# audio_webcam_final.net
KiCad netlist of a schematic drawn in EAGLE
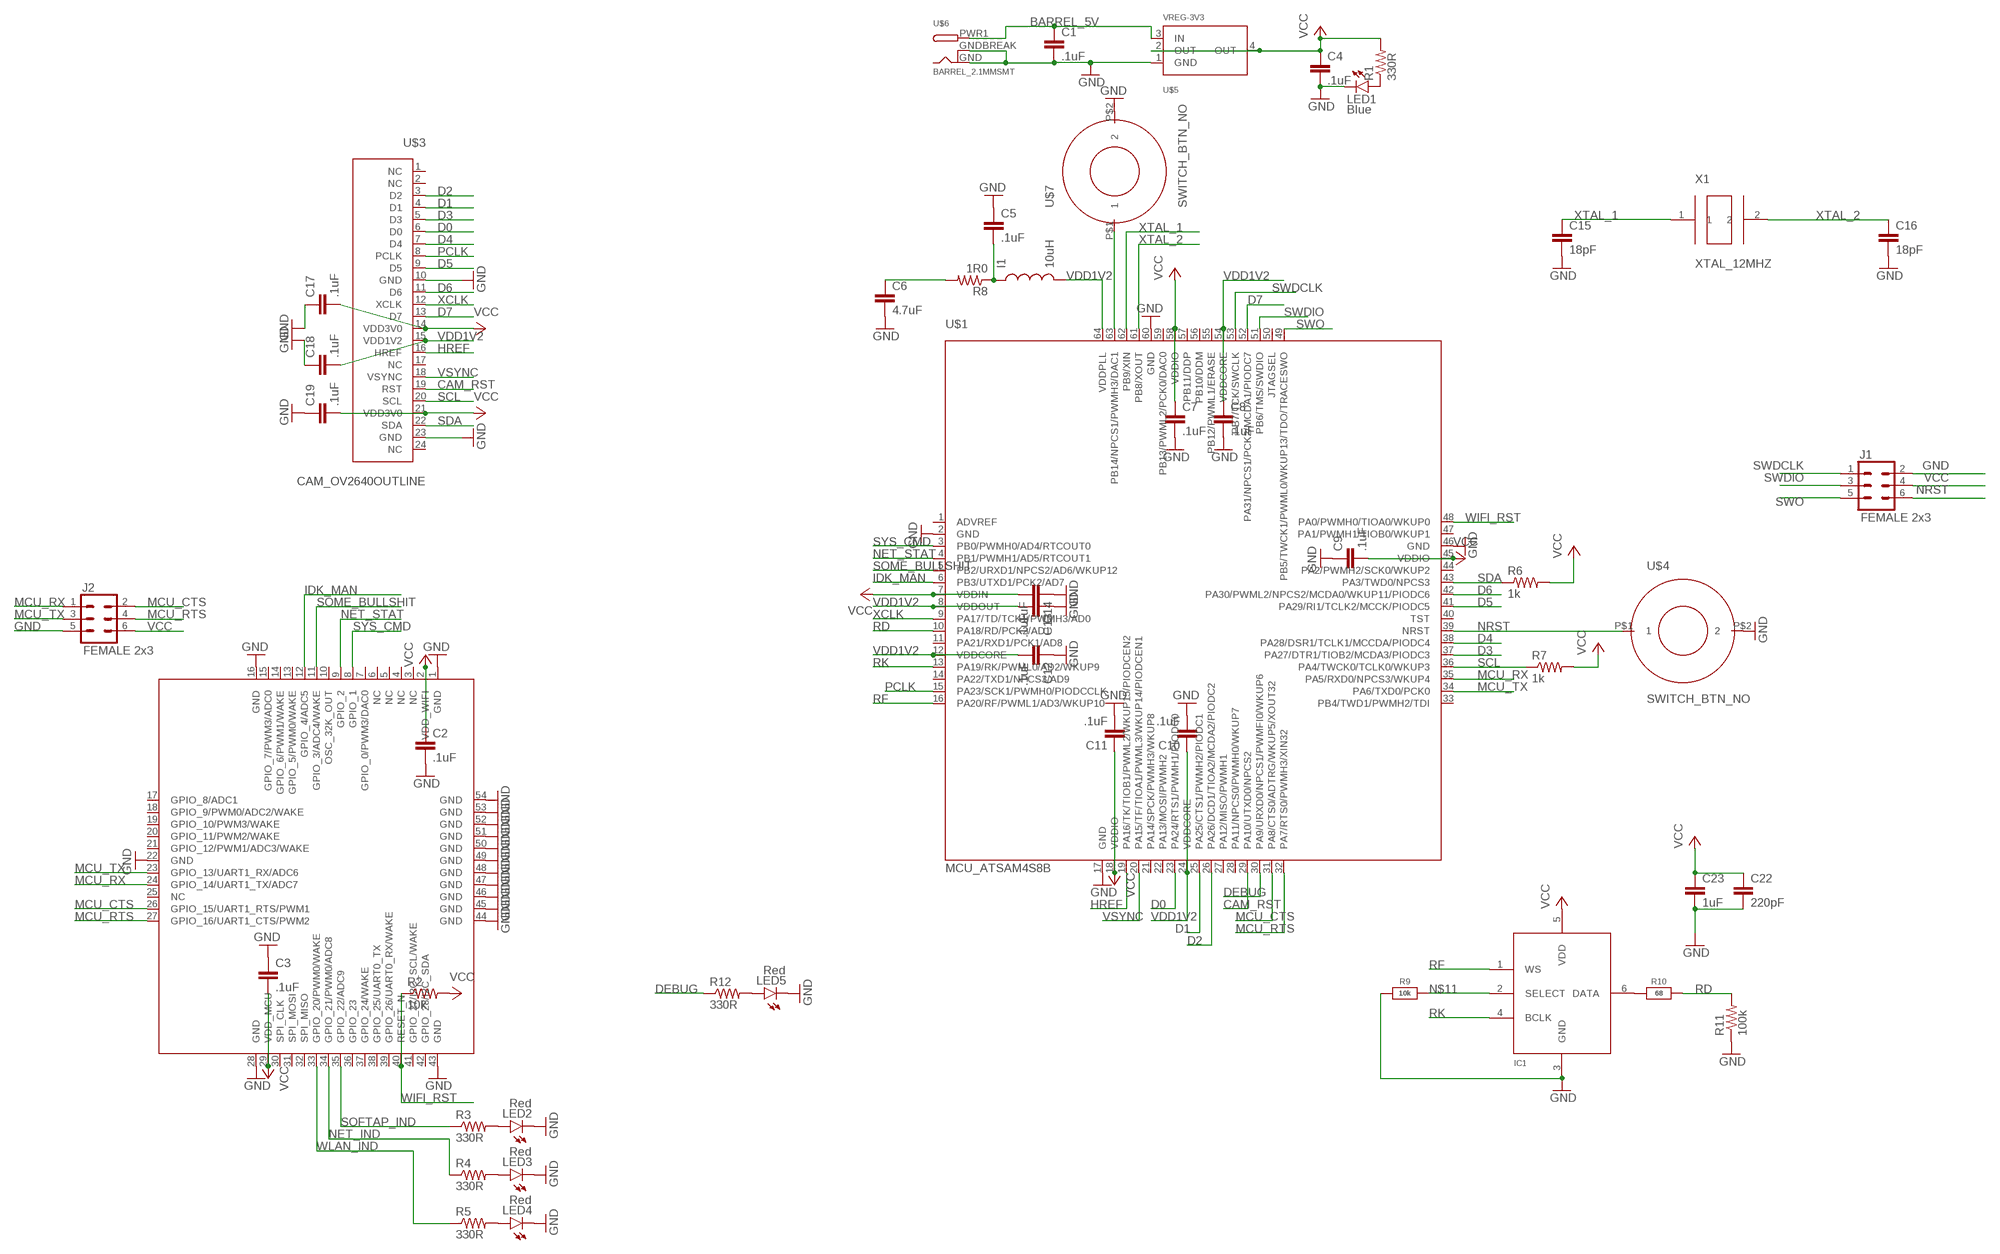
[diagram p0: schematic, sheet 1]

(export (version "E")
  (design (tool "Eeschema 10.0.6"))
  (components
    (comp (ref "C1")
      (value ".1uF")
      (footprint "eagle-import:0805")
      (libsource (lib "eagle-import") (part "CAP"))
    )
    (comp (ref "C2")
      (value ".1uF")
      (footprint "eagle-import:0805")
      (libsource (lib "eagle-import") (part "CAP"))
    )
    (comp (ref "C3")
      (value ".1uF")
      (footprint "eagle-import:0805")
      (libsource (lib "eagle-import") (part "CAP"))
    )
    (comp (ref "C4")
      (value ".1uF")
      (footprint "eagle-import:0805")
      (libsource (lib "eagle-import") (part "CAP"))
    )
    (comp (ref "C5")
      (value ".1uF")
      (footprint "eagle-import:0805")
      (libsource (lib "eagle-import") (part "CAP"))
    )
    (comp (ref "C6")
      (value "4.7uF")
      (footprint "eagle-import:0805")
      (libsource (lib "eagle-import") (part "CAP"))
    )
    (comp (ref "C7")
      (value ".1uF")
      (footprint "eagle-import:0805")
      (libsource (lib "eagle-import") (part "CAP"))
    )
    (comp (ref "C8")
      (value ".1uF")
      (footprint "eagle-import:0805")
      (libsource (lib "eagle-import") (part "CAP"))
    )
    (comp (ref "C9")
      (value ".1uF")
      (footprint "eagle-import:0805")
      (libsource (lib "eagle-import") (part "CAP"))
    )
    (comp (ref "C10")
      (value ".1uF")
      (footprint "eagle-import:0805")
      (libsource (lib "eagle-import") (part "CAP"))
    )
    (comp (ref "C11")
      (value ".1uF")
      (footprint "eagle-import:0805")
      (libsource (lib "eagle-import") (part "CAP"))
    )
    (comp (ref "C12")
      (value ".1uF")
      (footprint "eagle-import:0805")
      (libsource (lib "eagle-import") (part "CAP"))
    )
    (comp (ref "C13")
      (value ".1uF")
      (footprint "eagle-import:0805")
      (libsource (lib "eagle-import") (part "CAP"))
    )
    (comp (ref "C14")
      (value ".1uF")
      (footprint "eagle-import:0805")
      (libsource (lib "eagle-import") (part "CAP"))
    )
    (comp (ref "C15")
      (value "18pF")
      (footprint "eagle-import:0805")
      (libsource (lib "eagle-import") (part "CAP"))
    )
    (comp (ref "C16")
      (value "18pF")
      (footprint "eagle-import:0805")
      (libsource (lib "eagle-import") (part "CAP"))
    )
    (comp (ref "C17")
      (value ".1uF")
      (footprint "eagle-import:0805")
      (libsource (lib "eagle-import") (part "CAP"))
    )
    (comp (ref "C18")
      (value ".1uF")
      (footprint "eagle-import:0805")
      (libsource (lib "eagle-import") (part "CAP"))
    )
    (comp (ref "C19")
      (value ".1uF")
      (footprint "eagle-import:0805")
      (libsource (lib "eagle-import") (part "CAP"))
    )
    (comp (ref "C22")
      (value "220pF")
      (footprint "eagle-import:0805")
      (libsource (lib "eagle-import") (part "CAP"))
    )
    (comp (ref "C23")
      (value "1uF")
      (footprint "eagle-import:0805")
      (libsource (lib "eagle-import") (part "CAP"))
    )
    (comp (ref "I1")
      (value "10uH")
      (footprint "eagle-import:0805")
      (libsource (lib "eagle-import") (part "IND"))
    )
    (comp (ref "IC1")
      (value "MIC_I2S_SPH0645")
      (footprint "eagle-import:SPH0645LM4H")
      (libsource (lib "eagle-import") (part "MIC_I2S_SPH0645"))
    )
    (comp (ref "J1")
      (value "FEMALE 2x3")
      (footprint "eagle-import:2X3")
      (libsource (lib "eagle-import") (part "CONN_03X2FEMALE"))
    )
    (comp (ref "J2")
      (value "FEMALE 2x3")
      (footprint "eagle-import:2X3")
      (libsource (lib "eagle-import") (part "CONN_03X2FEMALE"))
    )
    (comp (ref "LED1")
      (value "Blue")
      (footprint "eagle-import:LED-0603")
      (libsource (lib "eagle-import") (part "LED0603"))
    )
    (comp (ref "LED2")
      (value "Red")
      (footprint "eagle-import:LED-0603")
      (libsource (lib "eagle-import") (part "LED0603"))
    )
    (comp (ref "LED3")
      (value "Red")
      (footprint "eagle-import:LED-0603")
      (libsource (lib "eagle-import") (part "LED0603"))
    )
    (comp (ref "LED4")
      (value "Red")
      (footprint "eagle-import:LED-0603")
      (libsource (lib "eagle-import") (part "LED0603"))
    )
    (comp (ref "LED5")
      (value "Red")
      (footprint "eagle-import:LED-0603")
      (libsource (lib "eagle-import") (part "LED0603"))
    )
    (comp (ref "R1")
      (value "330R")
      (footprint "eagle-import:0805")
      (libsource (lib "eagle-import") (part "RES"))
    )
    (comp (ref "R2")
      (value "10k")
      (footprint "eagle-import:0805")
      (libsource (lib "eagle-import") (part "RES"))
    )
    (comp (ref "R3")
      (value "330R")
      (footprint "eagle-import:0805")
      (libsource (lib "eagle-import") (part "RES"))
    )
    (comp (ref "R4")
      (value "330R")
      (footprint "eagle-import:0805")
      (libsource (lib "eagle-import") (part "RES"))
    )
    (comp (ref "R5")
      (value "330R")
      (footprint "eagle-import:0805")
      (libsource (lib "eagle-import") (part "RES"))
    )
    (comp (ref "R6")
      (value "1k")
      (footprint "eagle-import:0805")
      (libsource (lib "eagle-import") (part "RES"))
    )
    (comp (ref "R7")
      (value "1k")
      (footprint "eagle-import:0805")
      (libsource (lib "eagle-import") (part "RES"))
    )
    (comp (ref "R8")
      (value "1R0")
      (footprint "eagle-import:0805")
      (libsource (lib "eagle-import") (part "RES"))
    )
    (comp (ref "R9")
      (value "10k")
      (footprint "eagle-import:0603-NO")
      (libsource (lib "eagle-import") (part "RESISTOR_0603_NOOUT"))
    )
    (comp (ref "R10")
      (value "68")
      (footprint "eagle-import:0603-NO")
      (libsource (lib "eagle-import") (part "RESISTOR_0603_NOOUT"))
    )
    (comp (ref "R11")
      (value "100k")
      (footprint "eagle-import:0805")
      (libsource (lib "eagle-import") (part "RES"))
    )
    (comp (ref "R12")
      (value "330R")
      (footprint "eagle-import:0805")
      (libsource (lib "eagle-import") (part "RES"))
    )
    (comp (ref "U$1")
      (value "MCU_ATSAM4S8B")
      (footprint "eagle-import:QFP50P1200X1200X160-64N")
      (libsource (lib "eagle-import") (part "MCU_ATSAM4S8B"))
    )
    (comp (ref "U$2")
      (value "WIFI_AMW004")
      (footprint "eagle-import:AMW004")
      (libsource (lib "eagle-import") (part "WIFI_AMW004"))
    )
    (comp (ref "U$3")
      (value "CAM_OV2640OUTLINE")
      (footprint "eagle-import:CAM_CONN")
      (libsource (lib "eagle-import") (part "CAM_OV2640OUTLINE"))
    )
    (comp (ref "U$4")
      (value "SWITCH_BTN_NO")
      (footprint "eagle-import:BTN_2")
      (libsource (lib "eagle-import") (part "SWITCH_BTN_NO"))
    )
    (comp (ref "U$5")
      (value "VREG-3V3")
      (footprint "eagle-import:R-PDSO-G4_TI")
      (libsource (lib "eagle-import") (part "VREG-3V3"))
    )
    (comp (ref "U$6")
      (value "BARREL_2.1MMSMT")
      (footprint "eagle-import:DCJACK_2MM_SMT")
      (libsource (lib "eagle-import") (part "BARREL_2.1MMSMT"))
    )
    (comp (ref "U$7")
      (value "SWITCH_BTN_NO")
      (footprint "eagle-import:BTN_2")
      (libsource (lib "eagle-import") (part "SWITCH_BTN_NO"))
    )
    (comp (ref "X1")
      (value "XTAL_12MHZ")
      (footprint "eagle-import:ABM7-16.000MHZ-D2Y-T")
      (libsource (lib "eagle-import") (part "XTAL_12MHZ"))
    )
  )
  (nets
    (net (code "1") (name "/BARREL_5V") (class "Default")
      (node (ref "C1") (pin "1") (pinfunction "1_1") (pintype "passive"))
      (node (ref "U$5") (pin "3") (pinfunction "IN_3") (pintype "bidirectional"))
      (node (ref "U$6") (pin "PWR1") (pinfunction "PWR_PWR1") (pintype "power_in"))
    )
    (net (code "2") (name "/CAM_RST") (class "Default")
      (node (ref "U$1") (pin "29") (pinfunction "PA10/UTXD0/NPCS2_29") (pintype "bidirectional"))
      (node (ref "U$3") (pin "19") (pinfunction "RST_19") (pintype "bidirectional"))
    )
    (net (code "3") (name "/D0") (class "Default")
      (node (ref "U$1") (pin "23") (pinfunction "PA24/RTS1/PWMH1/PIODC0_23") (pintype "bidirectional"))
      (node (ref "U$3") (pin "6") (pinfunction "D0_6") (pintype "bidirectional"))
    )
    (net (code "4") (name "/D1") (class "Default")
      (node (ref "U$1") (pin "25") (pinfunction "PA25/CTS1/PWMH2/PIODC1_25") (pintype "bidirectional"))
      (node (ref "U$3") (pin "4") (pinfunction "D1_4") (pintype "bidirectional"))
    )
    (net (code "5") (name "/D2") (class "Default")
      (node (ref "U$1") (pin "26") (pinfunction "PA26/DCD1/TIOA2/MCDA2/PIODC2_26") (pintype "bidirectional"))
      (node (ref "U$3") (pin "3") (pinfunction "D2_3") (pintype "bidirectional"))
    )
    (net (code "6") (name "/D3") (class "Default")
      (node (ref "U$1") (pin "37") (pinfunction "PA27/DTR1/TIOB2/MCDA3/PIODC3_37") (pintype "bidirectional"))
      (node (ref "U$3") (pin "5") (pinfunction "D3_5") (pintype "bidirectional"))
    )
    (net (code "7") (name "/D4") (class "Default")
      (node (ref "U$1") (pin "38") (pinfunction "PA28/DSR1/TCLK1/MCCDA/PIODC4_38") (pintype "bidirectional"))
      (node (ref "U$3") (pin "7") (pinfunction "D4_7") (pintype "bidirectional"))
    )
    (net (code "8") (name "/D5") (class "Default")
      (node (ref "U$1") (pin "41") (pinfunction "PA29/RI1/TCLK2/MCCK/PIODC5_41") (pintype "bidirectional"))
      (node (ref "U$3") (pin "9") (pinfunction "D5_9") (pintype "bidirectional"))
    )
    (net (code "9") (name "/D6") (class "Default")
      (node (ref "U$1") (pin "42") (pinfunction "PA30/PWML2/NPCS2/MCDA0/WKUP11/PIODC6_42") (pintype "bidirectional"))
      (node (ref "U$3") (pin "11") (pinfunction "D6_11") (pintype "bidirectional"))
    )
    (net (code "10") (name "/D7") (class "Default")
      (node (ref "U$1") (pin "52") (pinfunction "PA31/NPCS1/PCK2/MCDA1/PIODC7_52") (pintype "bidirectional"))
      (node (ref "U$3") (pin "13") (pinfunction "D7_13") (pintype "bidirectional"))
    )
    (net (code "11") (name "/DEBUG") (class "Default")
      (node (ref "R12") (pin "1") (pinfunction "1_1") (pintype "passive"))
      (node (ref "U$1") (pin "30") (pinfunction "PA9/URXD0/NPCS1/PWMFI0/WKUP6_30") (pintype "bidirectional"))
    )
    (net (code "12") (name "/HREF") (class "Default")
      (node (ref "U$1") (pin "19") (pinfunction "PA16/TK/TIOB1/PWML2/WKUP15/PIODCEN2_19") (pintype "bidirectional"))
      (node (ref "U$3") (pin "16") (pinfunction "HREF_16") (pintype "bidirectional"))
    )
    (net (code "13") (name "/IDK_MAN") (class "Default")
      (node (ref "U$1") (pin "6") (pinfunction "PB3/UTXD1/PCK2/AD7_6") (pintype "bidirectional"))
      (node (ref "U$2") (pin "12") (pinfunction "GPIO_4/ADC5_12") (pintype "bidirectional"))
    )
    (net (code "14") (name "/MCU_CTS") (class "Default")
      (node (ref "J2") (pin "2") (pinfunction "2_2") (pintype "bidirectional"))
      (node (ref "U$1") (pin "31") (pinfunction "PA8/CTS0/ADTRG/WKUP5/XOUT32_31") (pintype "bidirectional"))
      (node (ref "U$2") (pin "26") (pinfunction "GPIO_15/UART1_RTS/PWM1_26") (pintype "bidirectional"))
    )
    (net (code "15") (name "/MCU_RTS") (class "Default")
      (node (ref "J2") (pin "4") (pinfunction "4_4") (pintype "bidirectional"))
      (node (ref "U$1") (pin "32") (pinfunction "PA7/RTS0/PWMH3/XIN32_32") (pintype "bidirectional"))
      (node (ref "U$2") (pin "27") (pinfunction "GPIO_16/UART1_CTS/PWM2_27") (pintype "bidirectional"))
    )
    (net (code "16") (name "/MCU_RX") (class "Default")
      (node (ref "J2") (pin "1") (pinfunction "1_1") (pintype "bidirectional"))
      (node (ref "U$1") (pin "35") (pinfunction "PA5/RXD0/NPCS3/WKUP4_35") (pintype "bidirectional"))
      (node (ref "U$2") (pin "24") (pinfunction "GPIO_14/UART1_TX/ADC7_24") (pintype "bidirectional"))
    )
    (net (code "17") (name "/MCU_TX") (class "Default")
      (node (ref "J2") (pin "3") (pinfunction "3_3") (pintype "bidirectional"))
      (node (ref "U$1") (pin "34") (pinfunction "PA6/TXD0/PCK0_34") (pintype "bidirectional"))
      (node (ref "U$2") (pin "23") (pinfunction "GPIO_13/UART1_RX/ADC6_23") (pintype "bidirectional"))
    )
    (net (code "18") (name "/N$11") (class "Default")
      (node (ref "IC1") (pin "2") (pinfunction "SELECT_2") (pintype "input"))
      (node (ref "R9") (pin "2") (pinfunction "2_2") (pintype "passive"))
    )
    (net (code "19") (name "/NET_IND") (class "Default")
      (node (ref "R4") (pin "1") (pinfunction "1_1") (pintype "passive"))
      (node (ref "U$2") (pin "34") (pinfunction "GPIO_21/PWM0/ADC8_34") (pintype "bidirectional"))
    )
    (net (code "20") (name "/NET_STAT") (class "Default")
      (node (ref "U$1") (pin "4") (pinfunction "PB1/PWMH1/AD5/RTCOUT1_4") (pintype "bidirectional"))
      (node (ref "U$2") (pin "9") (pinfunction "GPIO_2_9") (pintype "bidirectional"))
    )
    (net (code "21") (name "/NRST") (class "Default")
      (node (ref "J1") (pin "6") (pinfunction "6_6") (pintype "bidirectional"))
      (node (ref "U$1") (pin "39") (pinfunction "NRST_39") (pintype "bidirectional"))
      (node (ref "U$4") (pin "P$1") (pinfunction "1_P$1") (pintype "bidirectional"))
    )
    (net (code "22") (name "/PCLK") (class "Default")
      (node (ref "U$1") (pin "15") (pinfunction "PA23/SCK1/PWMH0/PIODCCLK_15") (pintype "bidirectional"))
      (node (ref "U$3") (pin "8") (pinfunction "PCLK_8") (pintype "bidirectional"))
    )
    (net (code "23") (name "/RD") (class "Default")
      (node (ref "R10") (pin "2") (pinfunction "2_2") (pintype "passive"))
      (node (ref "R11") (pin "2") (pinfunction "2_2") (pintype "passive"))
      (node (ref "U$1") (pin "10") (pinfunction "PA18/RD/PCK2/AD1_10") (pintype "bidirectional"))
    )
    (net (code "24") (name "/RF") (class "Default")
      (node (ref "IC1") (pin "1") (pinfunction "WS_1") (pintype "input"))
      (node (ref "U$1") (pin "16") (pinfunction "PA20/RF/PWML1/AD3/WKUP10_16") (pintype "bidirectional"))
    )
    (net (code "25") (name "/RK") (class "Default")
      (node (ref "IC1") (pin "4") (pinfunction "BCLK_4") (pintype "input"))
      (node (ref "U$1") (pin "13") (pinfunction "PA19/RK/PWML0/AD2/WKUP9_13") (pintype "bidirectional"))
    )
    (net (code "26") (name "/SCL") (class "Default")
      (node (ref "R7") (pin "1") (pinfunction "1_1") (pintype "passive"))
      (node (ref "U$1") (pin "36") (pinfunction "PA4/TWCK0/TCLK0/WKUP3_36") (pintype "bidirectional"))
      (node (ref "U$3") (pin "20") (pinfunction "SCL_20") (pintype "bidirectional"))
    )
    (net (code "27") (name "/SDA") (class "Default")
      (node (ref "R6") (pin "1") (pinfunction "1_1") (pintype "passive"))
      (node (ref "U$1") (pin "43") (pinfunction "PA3/TWD0/NPCS3_43") (pintype "bidirectional"))
      (node (ref "U$3") (pin "22") (pinfunction "SDA_22") (pintype "bidirectional"))
    )
    (net (code "28") (name "/SOFTAP_IND") (class "Default")
      (node (ref "R3") (pin "1") (pinfunction "1_1") (pintype "passive"))
      (node (ref "U$2") (pin "35") (pinfunction "GPIO_22/ADC9_35") (pintype "bidirectional"))
    )
    (net (code "29") (name "/SOME_BULLSHIT") (class "Default")
      (node (ref "U$1") (pin "5") (pinfunction "PB2/URXD1/NPCS2/AD6/WKUP12_5") (pintype "bidirectional"))
      (node (ref "U$2") (pin "11") (pinfunction "GPIO_3/ADC4/WAKE_11") (pintype "bidirectional"))
    )
    (net (code "30") (name "/SWDCLK") (class "Default")
      (node (ref "J1") (pin "1") (pinfunction "1_1") (pintype "bidirectional"))
      (node (ref "U$1") (pin "53") (pinfunction "PB7/TCK/SWCLK_53") (pintype "bidirectional"))
    )
    (net (code "31") (name "/SWDIO") (class "Default")
      (node (ref "J1") (pin "3") (pinfunction "3_3") (pintype "bidirectional"))
      (node (ref "U$1") (pin "51") (pinfunction "PB6/TMS/SWDIO_51") (pintype "bidirectional"))
    )
    (net (code "32") (name "/SWO") (class "Default")
      (node (ref "J1") (pin "5") (pinfunction "5_5") (pintype "bidirectional"))
      (node (ref "U$1") (pin "49") (pinfunction "PB5/TWCK1/PWML0/WKUP13/TDO/TRACESWO_49") (pintype "bidirectional"))
    )
    (net (code "33") (name "/SYS_CMD") (class "Default")
      (node (ref "U$1") (pin "3") (pinfunction "PB0/PWMH0/AD4/RTCOUT0_3") (pintype "bidirectional"))
      (node (ref "U$2") (pin "8") (pinfunction "GPIO_1_8") (pintype "bidirectional"))
    )
    (net (code "34") (name "/VDD1V2") (class "Default")
      (node (ref "C10") (pin "1") (pinfunction "1_1") (pintype "passive"))
      (node (ref "C12") (pin "2") (pinfunction "2_2") (pintype "passive"))
      (node (ref "C13") (pin "2") (pinfunction "2_2") (pintype "passive"))
      (node (ref "C18") (pin "2") (pinfunction "2_2") (pintype "passive"))
      (node (ref "C8") (pin "1") (pinfunction "1_1") (pintype "passive"))
      (node (ref "I1") (pin "2") (pinfunction "2_2") (pintype "passive"))
      (node (ref "U$1") (pin "12") (pinfunction "VDDCORE_12") (pintype "bidirectional"))
      (node (ref "U$1") (pin "24") (pinfunction "VDDCORE_24") (pintype "bidirectional"))
      (node (ref "U$1") (pin "54") (pinfunction "VDDCORE_54") (pintype "bidirectional"))
      (node (ref "U$1") (pin "64") (pinfunction "VDDPLL_64") (pintype "bidirectional"))
      (node (ref "U$1") (pin "8") (pinfunction "VDDOUT_8") (pintype "bidirectional"))
      (node (ref "U$3") (pin "15") (pinfunction "VDD1V2_15") (pintype "bidirectional"))
    )
    (net (code "35") (name "/VSYNC") (class "Default")
      (node (ref "U$1") (pin "20") (pinfunction "PA15/TF/TIOA1/PWML3/WKUP14/PIODCEN1_20") (pintype "bidirectional"))
      (node (ref "U$3") (pin "18") (pinfunction "VSYNC_18") (pintype "bidirectional"))
    )
    (net (code "36") (name "/WIFI_RST") (class "Default")
      (node (ref "R2") (pin "1") (pinfunction "1_1") (pintype "passive"))
      (node (ref "U$1") (pin "48") (pinfunction "PA0/PWMH0/TIOA0/WKUP0_48") (pintype "bidirectional"))
      (node (ref "U$2") (pin "40") (pinfunction "RESET_N_40") (pintype "bidirectional"))
    )
    (net (code "37") (name "/WLAN_IND") (class "Default")
      (node (ref "R5") (pin "1") (pinfunction "1_1") (pintype "passive"))
      (node (ref "U$2") (pin "33") (pinfunction "GPIO_20/PWM0/WAKE_33") (pintype "bidirectional"))
    )
    (net (code "38") (name "/XCLK") (class "Default")
      (node (ref "U$1") (pin "9") (pinfunction "PA17/TD/TCK1/PWMH3/AD0_9") (pintype "bidirectional"))
      (node (ref "U$3") (pin "12") (pinfunction "XCLK_12") (pintype "bidirectional"))
    )
    (net (code "39") (name "/XTAL_1") (class "Default")
      (node (ref "C15") (pin "1") (pinfunction "1_1") (pintype "passive"))
      (node (ref "U$1") (pin "62") (pinfunction "PB9/XIN_62") (pintype "bidirectional"))
      (node (ref "X1") (pin "1") (pinfunction "1_1") (pintype "bidirectional"))
    )
    (net (code "40") (name "/XTAL_2") (class "Default")
      (node (ref "C16") (pin "1") (pinfunction "1_1") (pintype "passive"))
      (node (ref "U$1") (pin "61") (pinfunction "PB8/XOUT_61") (pintype "bidirectional"))
      (node (ref "X1") (pin "2") (pinfunction "2_2") (pintype "bidirectional"))
    )
    (net (code "41") (name "GND") (class "Default")
      (node (ref "C1") (pin "2") (pinfunction "2_2") (pintype "passive"))
      (node (ref "C10") (pin "2") (pinfunction "2_2") (pintype "passive"))
      (node (ref "C11") (pin "2") (pinfunction "2_2") (pintype "passive"))
      (node (ref "C12") (pin "1") (pinfunction "1_1") (pintype "passive"))
      (node (ref "C13") (pin "1") (pinfunction "1_1") (pintype "passive"))
      (node (ref "C14") (pin "1") (pinfunction "1_1") (pintype "passive"))
      (node (ref "C15") (pin "2") (pinfunction "2_2") (pintype "passive"))
      (node (ref "C16") (pin "2") (pinfunction "2_2") (pintype "passive"))
      (node (ref "C17") (pin "1") (pinfunction "1_1") (pintype "passive"))
      (node (ref "C18") (pin "1") (pinfunction "1_1") (pintype "passive"))
      (node (ref "C19") (pin "1") (pinfunction "1_1") (pintype "passive"))
      (node (ref "C2") (pin "2") (pinfunction "2_2") (pintype "passive"))
      (node (ref "C22") (pin "2") (pinfunction "2_2") (pintype "passive"))
      (node (ref "C23") (pin "2") (pinfunction "2_2") (pintype "passive"))
      (node (ref "C3") (pin "1") (pinfunction "1_1") (pintype "passive"))
      (node (ref "C4") (pin "2") (pinfunction "2_2") (pintype "passive"))
      (node (ref "C5") (pin "1") (pinfunction "1_1") (pintype "passive"))
      (node (ref "C6") (pin "2") (pinfunction "2_2") (pintype "passive"))
      (node (ref "C7") (pin "2") (pinfunction "2_2") (pintype "passive"))
      (node (ref "C8") (pin "2") (pinfunction "2_2") (pintype "passive"))
      (node (ref "C9") (pin "1") (pinfunction "1_1") (pintype "passive"))
      (node (ref "IC1") (pin "3") (pinfunction "GND_3") (pintype "power_in"))
      (node (ref "J1") (pin "2") (pinfunction "2_2") (pintype "bidirectional"))
      (node (ref "J2") (pin "5") (pinfunction "5_5") (pintype "bidirectional"))
      (node (ref "LED1") (pin "C") (pinfunction "C_C") (pintype "passive"))
      (node (ref "LED2") (pin "C") (pinfunction "C_C") (pintype "passive"))
      (node (ref "LED3") (pin "C") (pinfunction "C_C") (pintype "passive"))
      (node (ref "LED4") (pin "C") (pinfunction "C_C") (pintype "passive"))
      (node (ref "LED5") (pin "C") (pinfunction "C_C") (pintype "passive"))
      (node (ref "R11") (pin "1") (pinfunction "1_1") (pintype "passive"))
      (node (ref "R9") (pin "1") (pinfunction "1_1") (pintype "passive"))
      (node (ref "U$1") (pin "17") (pinfunction "GND_17") (pintype "bidirectional"))
      (node (ref "U$1") (pin "2") (pinfunction "GND_2") (pintype "bidirectional"))
      (node (ref "U$1") (pin "46") (pinfunction "GND_46") (pintype "bidirectional"))
      (node (ref "U$1") (pin "60") (pinfunction "GND_60") (pintype "bidirectional"))
      (node (ref "U$2") (pin "1") (pinfunction "GND_1") (pintype "bidirectional"))
      (node (ref "U$2") (pin "16") (pinfunction "GND_16") (pintype "bidirectional"))
      (node (ref "U$2") (pin "22") (pinfunction "GND_22") (pintype "bidirectional"))
      (node (ref "U$2") (pin "28") (pinfunction "GND_28") (pintype "bidirectional"))
      (node (ref "U$2") (pin "43") (pinfunction "GND_43") (pintype "bidirectional"))
      (node (ref "U$2") (pin "44") (pinfunction "GND_44") (pintype "bidirectional"))
      (node (ref "U$2") (pin "45") (pinfunction "GND_45") (pintype "bidirectional"))
      (node (ref "U$2") (pin "46") (pinfunction "GND_46") (pintype "bidirectional"))
      (node (ref "U$2") (pin "47") (pinfunction "GND_47") (pintype "bidirectional"))
      (node (ref "U$2") (pin "48") (pinfunction "GND_48") (pintype "bidirectional"))
      (node (ref "U$2") (pin "49") (pinfunction "GND_49") (pintype "bidirectional"))
      (node (ref "U$2") (pin "50") (pinfunction "GND_50") (pintype "bidirectional"))
      (node (ref "U$2") (pin "51") (pinfunction "GND_51") (pintype "bidirectional"))
      (node (ref "U$2") (pin "52") (pinfunction "GND_52") (pintype "bidirectional"))
      (node (ref "U$2") (pin "53") (pinfunction "GND_53") (pintype "bidirectional"))
      (node (ref "U$2") (pin "54") (pinfunction "GND_54") (pintype "bidirectional"))
      (node (ref "U$3") (pin "10") (pinfunction "GND_10") (pintype "bidirectional"))
      (node (ref "U$3") (pin "23") (pinfunction "GND_23") (pintype "bidirectional"))
      (node (ref "U$4") (pin "P$2") (pinfunction "2_P$2") (pintype "bidirectional"))
      (node (ref "U$5") (pin "1") (pinfunction "GND_1") (pintype "bidirectional"))
      (node (ref "U$6") (pin "GND") (pinfunction "GND_GND") (pintype "power_in"))
      (node (ref "U$6") (pin "GNDBREAK") (pinfunction "GNDBREAK_GNDBREAK") (pintype "power_in"))
      (node (ref "U$7") (pin "P$2") (pinfunction "2_P$2") (pintype "bidirectional"))
    )
    (net (code "42") (name "Net-(C5-Pad2)") (class "Default")
      (node (ref "C5") (pin "2") (pinfunction "2_2") (pintype "passive"))
      (node (ref "I1") (pin "1") (pinfunction "1_1") (pintype "passive"))
      (node (ref "R8") (pin "1") (pinfunction "1_1") (pintype "passive"))
    )
    (net (code "43") (name "Net-(C6-Pad1)") (class "Default")
      (node (ref "C6") (pin "1") (pinfunction "1_1") (pintype "passive"))
      (node (ref "R8") (pin "2") (pinfunction "2_2") (pintype "passive"))
    )
    (net (code "44") (name "Net-(IC1-DATA)") (class "Default")
      (node (ref "IC1") (pin "6") (pinfunction "DATA_6") (pintype "output"))
      (node (ref "R10") (pin "1") (pinfunction "1_1") (pintype "passive"))
    )
    (net (code "45") (name "Net-(LED1-PadA)") (class "Default")
      (node (ref "LED1") (pin "A") (pinfunction "A_A") (pintype "passive"))
      (node (ref "R1") (pin "1") (pinfunction "1_1") (pintype "passive"))
    )
    (net (code "46") (name "Net-(LED2-PadA)") (class "Default")
      (node (ref "LED2") (pin "A") (pinfunction "A_A") (pintype "passive"))
      (node (ref "R3") (pin "2") (pinfunction "2_2") (pintype "passive"))
    )
    (net (code "47") (name "Net-(LED3-PadA)") (class "Default")
      (node (ref "LED3") (pin "A") (pinfunction "A_A") (pintype "passive"))
      (node (ref "R4") (pin "2") (pinfunction "2_2") (pintype "passive"))
    )
    (net (code "48") (name "Net-(LED4-PadA)") (class "Default")
      (node (ref "LED4") (pin "A") (pinfunction "A_A") (pintype "passive"))
      (node (ref "R5") (pin "2") (pinfunction "2_2") (pintype "passive"))
    )
    (net (code "49") (name "Net-(LED5-PadA)") (class "Default")
      (node (ref "LED5") (pin "A") (pinfunction "A_A") (pintype "passive"))
      (node (ref "R12") (pin "2") (pinfunction "2_2") (pintype "passive"))
    )
    (net (code "50") (name "Net-(U$1-PB14{slash}NPCS1{slash}PWMH3{slash}DAC1)") (class "Default")
      (node (ref "U$1") (pin "63") (pinfunction "PB14/NPCS1/PWMH3/DAC1_63") (pintype "bidirectional"))
      (node (ref "U$7") (pin "P$1") (pinfunction "1_P$1") (pintype "bidirectional"))
    )
    (net (code "51") (name "VCC") (class "Default")
      (node (ref "C11") (pin "1") (pinfunction "1_1") (pintype "passive"))
      (node (ref "C14") (pin "2") (pinfunction "2_2") (pintype "passive"))
      (node (ref "C17") (pin "2") (pinfunction "2_2") (pintype "passive"))
      (node (ref "C19") (pin "2") (pinfunction "2_2") (pintype "passive"))
      (node (ref "C2") (pin "1") (pinfunction "1_1") (pintype "passive"))
      (node (ref "C22") (pin "1") (pinfunction "1_1") (pintype "passive"))
      (node (ref "C23") (pin "1") (pinfunction "1_1") (pintype "passive"))
      (node (ref "C3") (pin "2") (pinfunction "2_2") (pintype "passive"))
      (node (ref "C4") (pin "1") (pinfunction "1_1") (pintype "passive"))
      (node (ref "C7") (pin "1") (pinfunction "1_1") (pintype "passive"))
      (node (ref "C9") (pin "2") (pinfunction "2_2") (pintype "passive"))
      (node (ref "IC1") (pin "5") (pinfunction "VDD_5") (pintype "power_in"))
      (node (ref "J1") (pin "4") (pinfunction "4_4") (pintype "bidirectional"))
      (node (ref "J2") (pin "6") (pinfunction "6_6") (pintype "bidirectional"))
      (node (ref "R1") (pin "2") (pinfunction "2_2") (pintype "passive"))
      (node (ref "R2") (pin "2") (pinfunction "2_2") (pintype "passive"))
      (node (ref "R6") (pin "2") (pinfunction "2_2") (pintype "passive"))
      (node (ref "R7") (pin "2") (pinfunction "2_2") (pintype "passive"))
      (node (ref "U$1") (pin "18") (pinfunction "VDDIO_18") (pintype "bidirectional"))
      (node (ref "U$1") (pin "45") (pinfunction "VDDIO_45") (pintype "bidirectional"))
      (node (ref "U$1") (pin "58") (pinfunction "VDDIO_58") (pintype "bidirectional"))
      (node (ref "U$1") (pin "7") (pinfunction "VDDIN_7") (pintype "bidirectional"))
      (node (ref "U$2") (pin "2") (pinfunction "VDD_WIFI_2") (pintype "bidirectional"))
      (node (ref "U$2") (pin "29") (pinfunction "VDD_MCU_29") (pintype "bidirectional"))
      (node (ref "U$3") (pin "14") (pinfunction "VDD3V0_14") (pintype "bidirectional"))
      (node (ref "U$3") (pin "21") (pinfunction "VDD3V0_21") (pintype "bidirectional"))
      (node (ref "U$5") (pin "2") (pinfunction "OUT_2") (pintype "bidirectional"))
      (node (ref "U$5") (pin "4") (pinfunction "OUT_4") (pintype "bidirectional"))
    )
    (net (code "52") (name "unconnected-(U$1-ADVREF-Pad1)") (class "Default")
      (node (ref "U$1") (pin "1") (pinfunction "ADVREF_1") (pintype "bidirectional"))
    )
    (net (code "53") (name "unconnected-(U$1-JTAGSEL-Pad50)") (class "Default")
      (node (ref "U$1") (pin "50") (pinfunction "JTAGSEL_50") (pintype "bidirectional"))
    )
    (net (code "54") (name "unconnected-(U$1-PA1{slash}PWMH1{slash}TIOB0{slash}WKUP1-Pad47)") (class "Default")
      (node (ref "U$1") (pin "47") (pinfunction "PA1/PWMH1/TIOB0/WKUP1_47") (pintype "bidirectional"))
    )
    (net (code "55") (name "unconnected-(U$1-PA2{slash}PWMH2{slash}SCK0{slash}WKUP2-Pad44)") (class "Default")
      (node (ref "U$1") (pin "44") (pinfunction "PA2/PWMH2/SCK0/WKUP2_44") (pintype "bidirectional"))
    )
    (net (code "56") (name "unconnected-(U$1-PA11{slash}NPCS0{slash}PWMH0{slash}WKUP7-Pad28)") (class "Default")
      (node (ref "U$1") (pin "28") (pinfunction "PA11/NPCS0/PWMH0/WKUP7_28") (pintype "bidirectional"))
    )
    (net (code "57") (name "unconnected-(U$1-PA12{slash}MISO{slash}PWMH1-Pad27)") (class "Default")
      (node (ref "U$1") (pin "27") (pinfunction "PA12/MISO/PWMH1_27") (pintype "bidirectional"))
    )
    (net (code "58") (name "unconnected-(U$1-PA13{slash}MOSI{slash}PWMH2-Pad22)") (class "Default")
      (node (ref "U$1") (pin "22") (pinfunction "PA13/MOSI/PWMH2_22") (pintype "bidirectional"))
    )
    (net (code "59") (name "unconnected-(U$1-PA14{slash}SPCK{slash}PWMH3{slash}WKUP8-Pad21)") (class "Default")
      (node (ref "U$1") (pin "21") (pinfunction "PA14/SPCK/PWMH3/WKUP8_21") (pintype "bidirectional"))
    )
    (net (code "60") (name "unconnected-(U$1-PA21{slash}RXD1{slash}PCK1{slash}AD8-Pad11)") (class "Default")
      (node (ref "U$1") (pin "11") (pinfunction "PA21/RXD1/PCK1/AD8_11") (pintype "bidirectional"))
    )
    (net (code "61") (name "unconnected-(U$1-PA22{slash}TXD1{slash}NPCS3{slash}AD9-Pad14)") (class "Default")
      (node (ref "U$1") (pin "14") (pinfunction "PA22/TXD1/NPCS3/AD9_14") (pintype "bidirectional"))
    )
    (net (code "62") (name "unconnected-(U$1-PB4{slash}TWD1{slash}PWMH2{slash}TDI-Pad33)") (class "Default")
      (node (ref "U$1") (pin "33") (pinfunction "PB4/TWD1/PWMH2/TDI_33") (pintype "bidirectional"))
    )
    (net (code "63") (name "unconnected-(U$1-PB10{slash}DDM-Pad56)") (class "Default")
      (node (ref "U$1") (pin "56") (pinfunction "PB10/DDM_56") (pintype "bidirectional"))
    )
    (net (code "64") (name "unconnected-(U$1-PB11{slash}DDP-Pad57)") (class "Default")
      (node (ref "U$1") (pin "57") (pinfunction "PB11/DDP_57") (pintype "bidirectional"))
    )
    (net (code "65") (name "unconnected-(U$1-PB12{slash}PWML1{slash}ERASE-Pad55)") (class "Default")
      (node (ref "U$1") (pin "55") (pinfunction "PB12/PWML1/ERASE_55") (pintype "bidirectional"))
    )
    (net (code "66") (name "unconnected-(U$1-PB13{slash}PWML2{slash}PCK0{slash}DAC0-Pad59)") (class "Default")
      (node (ref "U$1") (pin "59") (pinfunction "PB13/PWML2/PCK0/DAC0_59") (pintype "bidirectional"))
    )
    (net (code "67") (name "unconnected-(U$1-TST-Pad40)") (class "Default")
      (node (ref "U$1") (pin "40") (pinfunction "TST_40") (pintype "bidirectional"))
    )
    (net (code "68") (name "unconnected-(U$2-GPIO_0{slash}PWM3{slash}DAC0-Pad7)") (class "Default")
      (node (ref "U$2") (pin "7") (pinfunction "GPIO_0/PWM3/DAC0_7") (pintype "bidirectional"))
    )
    (net (code "69") (name "unconnected-(U$2-GPIO_5{slash}PWM0{slash}WAKE-Pad13)") (class "Default")
      (node (ref "U$2") (pin "13") (pinfunction "GPIO_5/PWM0/WAKE_13") (pintype "bidirectional"))
    )
    (net (code "70") (name "unconnected-(U$2-GPIO_6{slash}PWM1{slash}WAKE-Pad14)") (class "Default")
      (node (ref "U$2") (pin "14") (pinfunction "GPIO_6/PWM1/WAKE_14") (pintype "bidirectional"))
    )
    (net (code "71") (name "unconnected-(U$2-GPIO_7{slash}PWM3{slash}ADC0-Pad15)") (class "Default")
      (node (ref "U$2") (pin "15") (pinfunction "GPIO_7/PWM3/ADC0_15") (pintype "bidirectional"))
    )
    (net (code "72") (name "unconnected-(U$2-GPIO_8{slash}ADC1-Pad17)") (class "Default")
      (node (ref "U$2") (pin "17") (pinfunction "GPIO_8/ADC1_17") (pintype "bidirectional"))
    )
    (net (code "73") (name "unconnected-(U$2-GPIO_9{slash}PWM0{slash}ADC2{slash}WAKE-Pad18)") (class "Default")
      (node (ref "U$2") (pin "18") (pinfunction "GPIO_9/PWM0/ADC2/WAKE_18") (pintype "bidirectional"))
    )
    (net (code "74") (name "unconnected-(U$2-GPIO_10{slash}PWM3{slash}WAKE-Pad19)") (class "Default")
      (node (ref "U$2") (pin "19") (pinfunction "GPIO_10/PWM3/WAKE_19") (pintype "bidirectional"))
    )
    (net (code "75") (name "unconnected-(U$2-GPIO_11{slash}PWM2{slash}WAKE-Pad20)") (class "Default")
      (node (ref "U$2") (pin "20") (pinfunction "GPIO_11/PWM2/WAKE_20") (pintype "bidirectional"))
    )
    (net (code "76") (name "unconnected-(U$2-GPIO_12{slash}PWM1{slash}ADC3{slash}WAKE-Pad21)") (class "Default")
      (node (ref "U$2") (pin "21") (pinfunction "GPIO_12/PWM1/ADC3/WAKE_21") (pintype "bidirectional"))
    )
    (net (code "77") (name "unconnected-(U$2-GPIO_23-Pad36)") (class "Default")
      (node (ref "U$2") (pin "36") (pinfunction "GPIO_23_36") (pintype "bidirectional"))
    )
    (net (code "78") (name "unconnected-(U$2-GPIO_24{slash}WAKE-Pad37)") (class "Default")
      (node (ref "U$2") (pin "37") (pinfunction "GPIO_24/WAKE_37") (pintype "bidirectional"))
    )
    (net (code "79") (name "unconnected-(U$2-GPIO_25{slash}UART0_TX-Pad38)") (class "Default")
      (node (ref "U$2") (pin "38") (pinfunction "GPIO_25/UART0_TX_38") (pintype "bidirectional"))
    )
    (net (code "80") (name "unconnected-(U$2-GPIO_26{slash}UART0_RX{slash}WAKE-Pad39)") (class "Default")
      (node (ref "U$2") (pin "39") (pinfunction "GPIO_26/UART0_RX/WAKE_39") (pintype "bidirectional"))
    )
    (net (code "81") (name "unconnected-(U$2-GPIO_27{slash}I2C_SCL{slash}WAKE-Pad41)") (class "Default")
      (node (ref "U$2") (pin "41") (pinfunction "GPIO_27/I2C_SCL/WAKE_41") (pintype "bidirectional"))
    )
    (net (code "82") (name "unconnected-(U$2-GPIO_28{slash}I2C_SDA-Pad42)") (class "Default")
      (node (ref "U$2") (pin "42") (pinfunction "GPIO_28/I2C_SDA_42") (pintype "bidirectional"))
    )
    (net (code "83") (name "unconnected-(U$2-NC-Pad3)") (class "Default")
      (node (ref "U$2") (pin "3") (pinfunction "NC_3") (pintype "bidirectional"))
    )
    (net (code "84") (name "unconnected-(U$2-NC-Pad4)") (class "Default")
      (node (ref "U$2") (pin "4") (pinfunction "NC_4") (pintype "bidirectional"))
    )
    (net (code "85") (name "unconnected-(U$2-NC-Pad5)") (class "Default")
      (node (ref "U$2") (pin "5") (pinfunction "NC_5") (pintype "bidirectional"))
    )
    (net (code "86") (name "unconnected-(U$2-NC-Pad6)") (class "Default")
      (node (ref "U$2") (pin "6") (pinfunction "NC_6") (pintype "bidirectional"))
    )
    (net (code "87") (name "unconnected-(U$2-NC-Pad25)") (class "Default")
      (node (ref "U$2") (pin "25") (pinfunction "NC_25") (pintype "bidirectional"))
    )
    (net (code "88") (name "unconnected-(U$2-OSC_32K_OUT-Pad10)") (class "Default")
      (node (ref "U$2") (pin "10") (pinfunction "OSC_32K_OUT_10") (pintype "bidirectional"))
    )
    (net (code "89") (name "unconnected-(U$2-SPI_CLK-Pad30)") (class "Default")
      (node (ref "U$2") (pin "30") (pinfunction "SPI_CLK_30") (pintype "bidirectional"))
    )
    (net (code "90") (name "unconnected-(U$2-SPI_MISO-Pad32)") (class "Default")
      (node (ref "U$2") (pin "32") (pinfunction "SPI_MISO_32") (pintype "bidirectional"))
    )
    (net (code "91") (name "unconnected-(U$2-SPI_MOSI-Pad31)") (class "Default")
      (node (ref "U$2") (pin "31") (pinfunction "SPI_MOSI_31") (pintype "bidirectional"))
    )
    (net (code "92") (name "unconnected-(U$3-NC-Pad1)") (class "Default")
      (node (ref "U$3") (pin "1") (pinfunction "NC_1") (pintype "bidirectional"))
    )
    (net (code "93") (name "unconnected-(U$3-NC-Pad2)") (class "Default")
      (node (ref "U$3") (pin "2") (pinfunction "NC_2") (pintype "bidirectional"))
    )
    (net (code "94") (name "unconnected-(U$3-NC-Pad17)") (class "Default")
      (node (ref "U$3") (pin "17") (pinfunction "NC_17") (pintype "bidirectional"))
    )
    (net (code "95") (name "unconnected-(U$3-NC-Pad24)") (class "Default")
      (node (ref "U$3") (pin "24") (pinfunction "NC_24") (pintype "bidirectional"))
    )
  )
)
